# TTGO_shield_revH.net
KiCad netlist of a schematic drawn in EAGLE
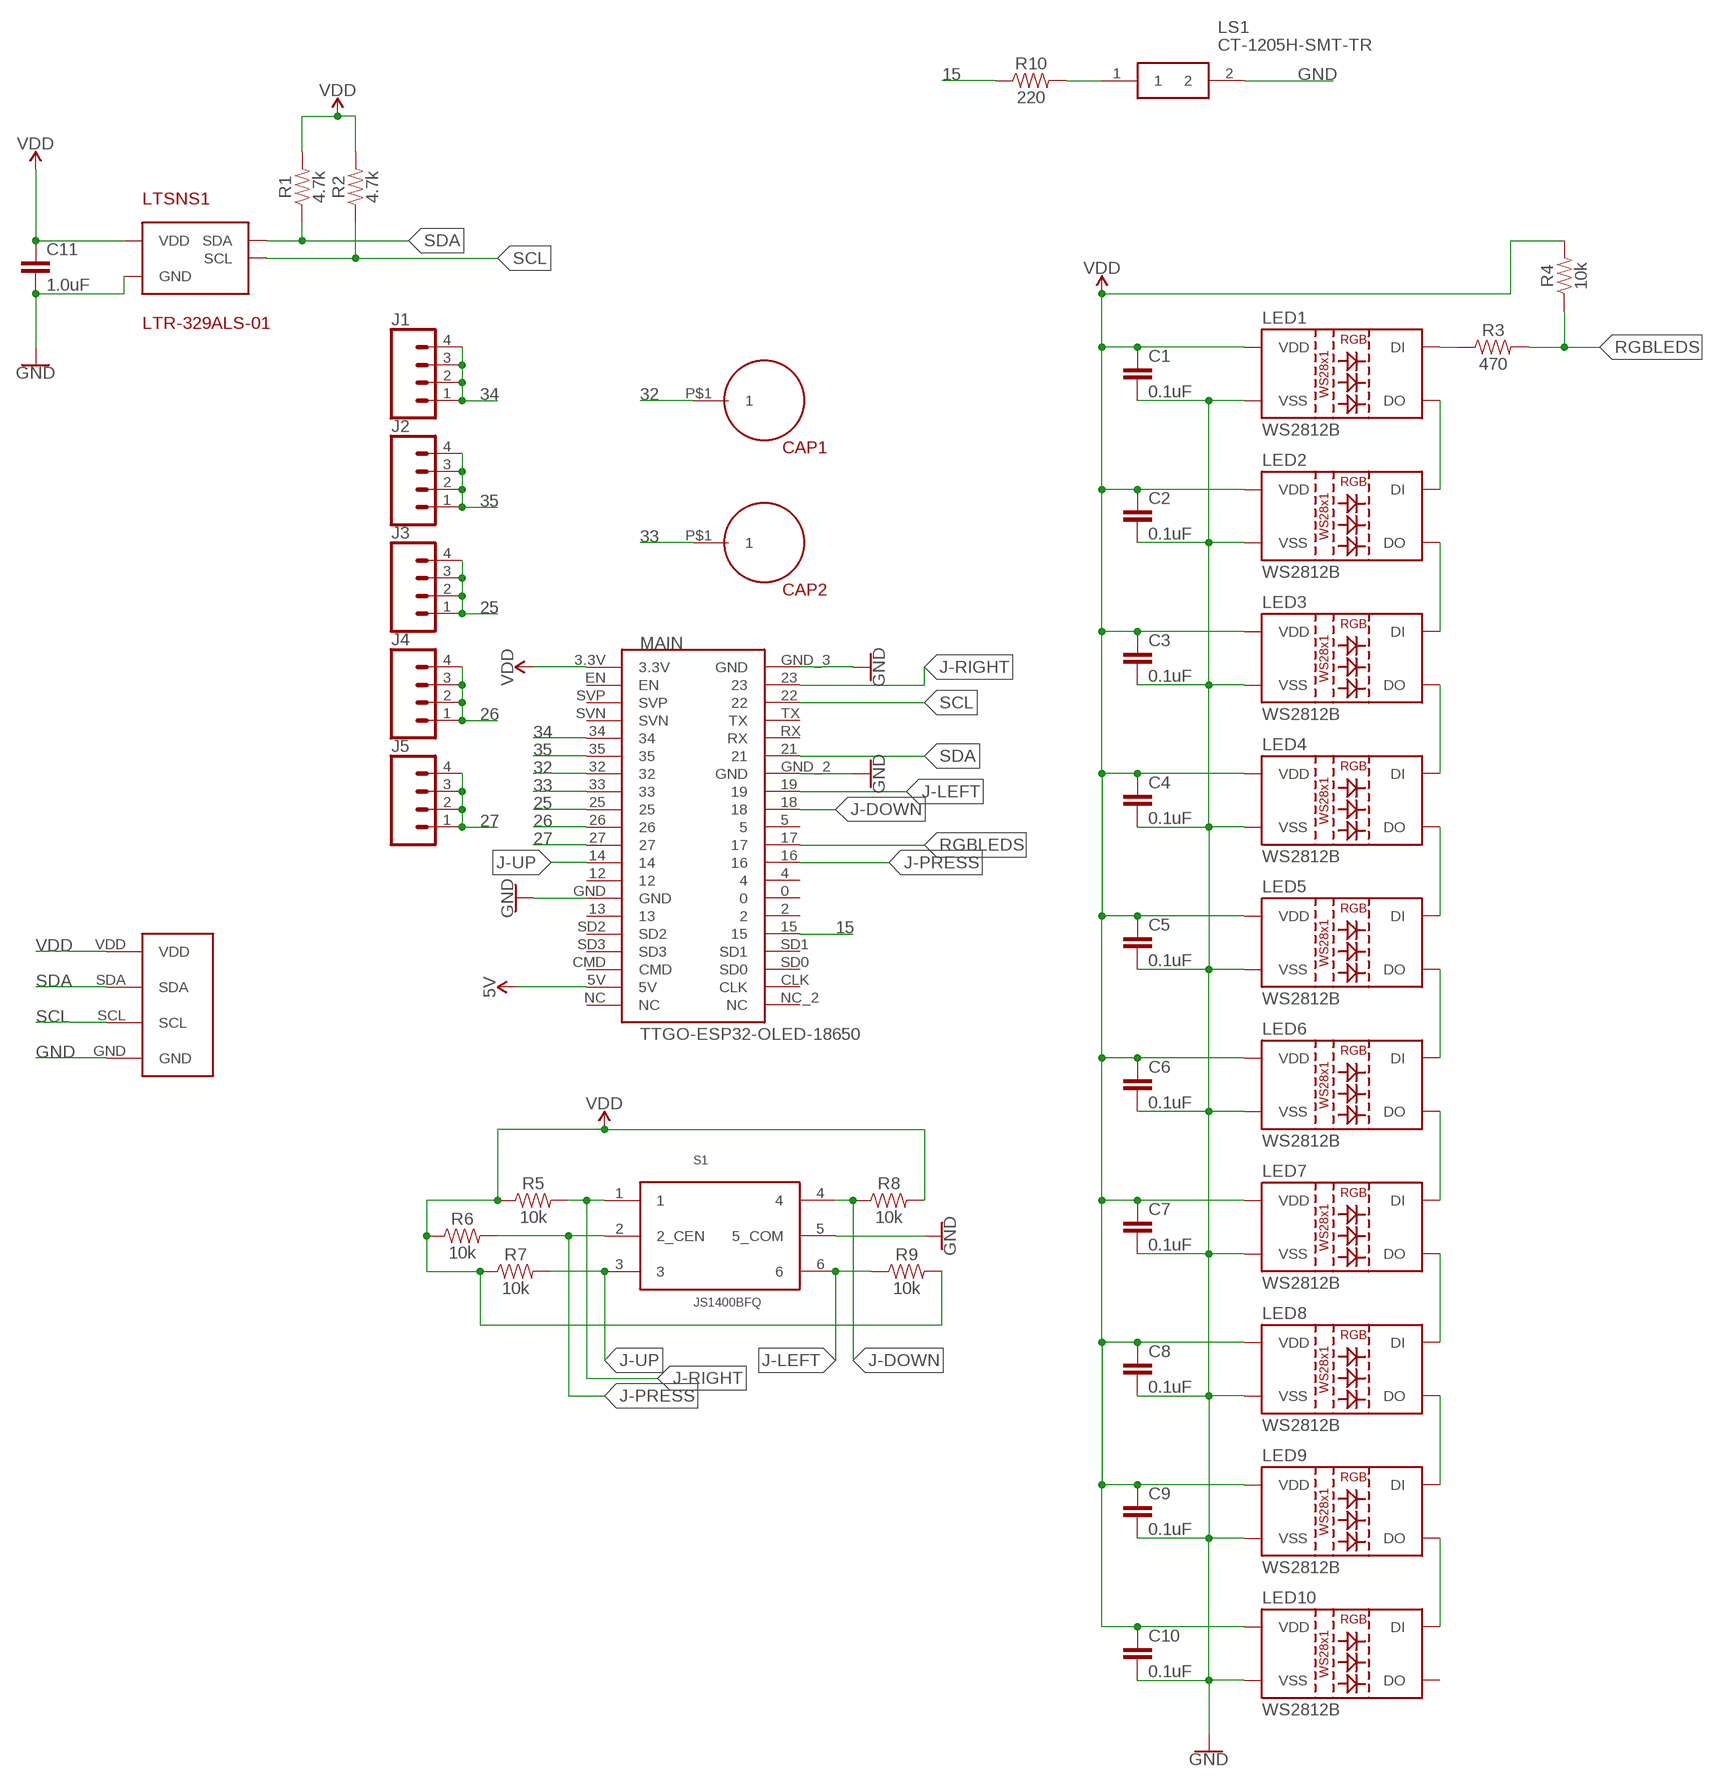
[diagram p0: schematic, sheet 1]

(export (version "E")
  (design (tool "Eeschema 10.0.6"))
  (components
    (comp (ref "C1")
      (value "0.1uF")
      (footprint "eagle-import:0603")
      (libsource (lib "eagle-import") (part "0.1UF-0603-25V-5%"))
    )
    (comp (ref "C2")
      (value "0.1uF")
      (footprint "eagle-import:0603")
      (libsource (lib "eagle-import") (part "0.1UF-0603-25V-5%"))
    )
    (comp (ref "C3")
      (value "0.1uF")
      (footprint "eagle-import:0603")
      (libsource (lib "eagle-import") (part "0.1UF-0603-25V-5%"))
    )
    (comp (ref "C4")
      (value "0.1uF")
      (footprint "eagle-import:0603")
      (libsource (lib "eagle-import") (part "0.1UF-0603-25V-5%"))
    )
    (comp (ref "C5")
      (value "0.1uF")
      (footprint "eagle-import:0603")
      (libsource (lib "eagle-import") (part "0.1UF-0603-25V-5%"))
    )
    (comp (ref "C6")
      (value "0.1uF")
      (footprint "eagle-import:0603")
      (libsource (lib "eagle-import") (part "0.1UF-0603-25V-5%"))
    )
    (comp (ref "C7")
      (value "0.1uF")
      (footprint "eagle-import:0603")
      (libsource (lib "eagle-import") (part "0.1UF-0603-25V-5%"))
    )
    (comp (ref "C8")
      (value "0.1uF")
      (footprint "eagle-import:0603")
      (libsource (lib "eagle-import") (part "0.1UF-0603-25V-5%"))
    )
    (comp (ref "C9")
      (value "0.1uF")
      (footprint "eagle-import:0603")
      (libsource (lib "eagle-import") (part "0.1UF-0603-25V-5%"))
    )
    (comp (ref "C10")
      (value "0.1uF")
      (footprint "eagle-import:0603")
      (libsource (lib "eagle-import") (part "0.1UF-0603-25V-5%"))
    )
    (comp (ref "C11")
      (value "1.0uF")
      (footprint "eagle-import:0805")
      (libsource (lib "eagle-import") (part "1.0UF-0805-25V-10%"))
    )
    (comp (ref "CAP1")
      (value "CAPSENSE_BUTTON")
      (footprint "eagle-import:CAPSENSE_BUTTON")
      (libsource (lib "eagle-import") (part "CAPSENSE_BUTTON"))
    )
    (comp (ref "CAP2")
      (value "CAPSENSE_BUTTON")
      (footprint "eagle-import:CAPSENSE_BUTTON")
      (libsource (lib "eagle-import") (part "CAPSENSE_BUTTON"))
    )
    (comp (ref "J1")
      (value "CONN_04LONGPADS")
      (footprint "eagle-import:1X04_LONGPADS")
      (libsource (lib "eagle-import") (part "CONN_04LONGPADS"))
    )
    (comp (ref "J2")
      (value "CONN_04LONGPADS")
      (footprint "eagle-import:1X04_LONGPADS")
      (libsource (lib "eagle-import") (part "CONN_04LONGPADS"))
    )
    (comp (ref "J3")
      (value "CONN_04LONGPADS")
      (footprint "eagle-import:1X04_LONGPADS")
      (libsource (lib "eagle-import") (part "CONN_04LONGPADS"))
    )
    (comp (ref "J4")
      (value "CONN_04LONGPADS")
      (footprint "eagle-import:1X04_LONGPADS")
      (libsource (lib "eagle-import") (part "CONN_04LONGPADS"))
    )
    (comp (ref "J5")
      (value "CONN_04LONGPADS")
      (footprint "eagle-import:1X04_LONGPADS")
      (libsource (lib "eagle-import") (part "CONN_04LONGPADS"))
    )
    (comp (ref "LED1")
      (value "WS2812B")
      (footprint "eagle-import:WS2812B")
      (libsource (lib "eagle-import") (part "WS2812B"))
    )
    (comp (ref "LED2")
      (value "WS2812B")
      (footprint "eagle-import:WS2812B")
      (libsource (lib "eagle-import") (part "WS2812B"))
    )
    (comp (ref "LED3")
      (value "WS2812B")
      (footprint "eagle-import:WS2812B")
      (libsource (lib "eagle-import") (part "WS2812B"))
    )
    (comp (ref "LED4")
      (value "WS2812B")
      (footprint "eagle-import:WS2812B")
      (libsource (lib "eagle-import") (part "WS2812B"))
    )
    (comp (ref "LED5")
      (value "WS2812B")
      (footprint "eagle-import:WS2812B")
      (libsource (lib "eagle-import") (part "WS2812B"))
    )
    (comp (ref "LED6")
      (value "WS2812B")
      (footprint "eagle-import:WS2812B")
      (libsource (lib "eagle-import") (part "WS2812B"))
    )
    (comp (ref "LED7")
      (value "WS2812B")
      (footprint "eagle-import:WS2812B")
      (libsource (lib "eagle-import") (part "WS2812B"))
    )
    (comp (ref "LED8")
      (value "WS2812B")
      (footprint "eagle-import:WS2812B")
      (libsource (lib "eagle-import") (part "WS2812B"))
    )
    (comp (ref "LED9")
      (value "WS2812B")
      (footprint "eagle-import:WS2812B")
      (libsource (lib "eagle-import") (part "WS2812B"))
    )
    (comp (ref "LED10")
      (value "WS2812B")
      (footprint "eagle-import:WS2812B")
      (libsource (lib "eagle-import") (part "WS2812B"))
    )
    (comp (ref "LS1")
      (value "CT-1205H-SMT-TR")
      (footprint "eagle-import:CT1205HSMTTR")
      (libsource (lib "eagle-import") (part "CT-1205H-SMT-TR"))
    )
    (comp (ref "LTSNS1")
      (value "LTR-329ALS-01")
      (footprint "eagle-import:CHIPLED-4")
      (libsource (lib "eagle-import") (part "LTR-329ALS-01"))
    )
    (comp (ref "MAIN")
      (value "TTGO-ESP32-OLED-18650")
      (footprint "eagle-import:TTGO-ESP32-OLED-18650")
      (libsource (lib "eagle-import") (part "TTGO-ESP32-OLED-18650"))
    )
    (comp (ref "R1")
      (value "4.7k")
      (footprint "eagle-import:0603")
      (libsource (lib "eagle-import") (part "4.7KOHM-0603-1/10W-1%"))
    )
    (comp (ref "R2")
      (value "4.7k")
      (footprint "eagle-import:0603")
      (libsource (lib "eagle-import") (part "4.7KOHM-0603-1/10W-1%"))
    )
    (comp (ref "R3")
      (value "470")
      (footprint "eagle-import:0603")
      (libsource (lib "eagle-import") (part "470OHM-0603-1/10W-1%"))
    )
    (comp (ref "R4")
      (value "10k")
      (footprint "eagle-import:0603")
      (libsource (lib "eagle-import") (part "10KOHM-0603-1/10W-1%"))
    )
    (comp (ref "R5")
      (value "10k")
      (footprint "eagle-import:0603")
      (libsource (lib "eagle-import") (part "10KOHM-0603-1/10W-1%"))
    )
    (comp (ref "R6")
      (value "10k")
      (footprint "eagle-import:0603")
      (libsource (lib "eagle-import") (part "10KOHM-0603-1/10W-1%"))
    )
    (comp (ref "R7")
      (value "10k")
      (footprint "eagle-import:0603")
      (libsource (lib "eagle-import") (part "10KOHM-0603-1/10W-1%"))
    )
    (comp (ref "R8")
      (value "10k")
      (footprint "eagle-import:0603")
      (libsource (lib "eagle-import") (part "10KOHM-0603-1/10W-1%"))
    )
    (comp (ref "R9")
      (value "10k")
      (footprint "eagle-import:0603")
      (libsource (lib "eagle-import") (part "10KOHM-0603-1/10W-1%"))
    )
    (comp (ref "R10")
      (value "220")
      (footprint "eagle-import:0603")
      (libsource (lib "eagle-import") (part "470OHM-0603-1/10W-1%"))
    )
    (comp (ref "S1")
      (value "JS1400BFQ")
      (footprint "eagle-import:JS1400BFQ")
      (libsource (lib "eagle-import") (part "JS1400BFQ"))
    )
    (comp (ref "U$2")
      (value "I2C-FEMALE-HEADER")
      (footprint "eagle-import:I2C-FEMALE-HEADER")
      (libsource (lib "eagle-import") (part "I2C-FEMALE-HEADER"))
    )
  )
  (nets
    (net (code "1") (name "/15") (class "Default")
      (node (ref "MAIN") (pin "15") (pinfunction "15_15") (pintype "bidirectional"))
      (node (ref "R10") (pin "1") (pinfunction "1_1") (pintype "passive"))
    )
    (net (code "2") (name "/25") (class "Default")
      (node (ref "J3") (pin "1") (pinfunction "1_1") (pintype "passive"))
      (node (ref "J3") (pin "2") (pinfunction "2_2") (pintype "passive"))
      (node (ref "J3") (pin "3") (pinfunction "3_3") (pintype "passive"))
      (node (ref "J3") (pin "4") (pinfunction "4_4") (pintype "passive"))
      (node (ref "MAIN") (pin "25") (pinfunction "25_25") (pintype "bidirectional"))
    )
    (net (code "3") (name "/26") (class "Default")
      (node (ref "J4") (pin "1") (pinfunction "1_1") (pintype "passive"))
      (node (ref "J4") (pin "2") (pinfunction "2_2") (pintype "passive"))
      (node (ref "J4") (pin "3") (pinfunction "3_3") (pintype "passive"))
      (node (ref "J4") (pin "4") (pinfunction "4_4") (pintype "passive"))
      (node (ref "MAIN") (pin "26") (pinfunction "26_26") (pintype "bidirectional"))
    )
    (net (code "4") (name "/27") (class "Default")
      (node (ref "J5") (pin "1") (pinfunction "1_1") (pintype "passive"))
      (node (ref "J5") (pin "2") (pinfunction "2_2") (pintype "passive"))
      (node (ref "J5") (pin "3") (pinfunction "3_3") (pintype "passive"))
      (node (ref "J5") (pin "4") (pinfunction "4_4") (pintype "passive"))
      (node (ref "MAIN") (pin "27") (pinfunction "27_27") (pintype "bidirectional"))
    )
    (net (code "5") (name "/32") (class "Default")
      (node (ref "CAP1") (pin "P$1") (pinfunction "1_P$1") (pintype "bidirectional"))
      (node (ref "MAIN") (pin "32") (pinfunction "32_32") (pintype "bidirectional"))
    )
    (net (code "6") (name "/33") (class "Default")
      (node (ref "CAP2") (pin "P$1") (pinfunction "1_P$1") (pintype "bidirectional"))
      (node (ref "MAIN") (pin "33") (pinfunction "33_33") (pintype "bidirectional"))
    )
    (net (code "7") (name "/34") (class "Default")
      (node (ref "J1") (pin "1") (pinfunction "1_1") (pintype "passive"))
      (node (ref "J1") (pin "2") (pinfunction "2_2") (pintype "passive"))
      (node (ref "J1") (pin "3") (pinfunction "3_3") (pintype "passive"))
      (node (ref "J1") (pin "4") (pinfunction "4_4") (pintype "passive"))
      (node (ref "MAIN") (pin "34") (pinfunction "34_34") (pintype "bidirectional"))
    )
    (net (code "8") (name "/35") (class "Default")
      (node (ref "J2") (pin "1") (pinfunction "1_1") (pintype "passive"))
      (node (ref "J2") (pin "2") (pinfunction "2_2") (pintype "passive"))
      (node (ref "J2") (pin "3") (pinfunction "3_3") (pintype "passive"))
      (node (ref "J2") (pin "4") (pinfunction "4_4") (pintype "passive"))
      (node (ref "MAIN") (pin "35") (pinfunction "35_35") (pintype "bidirectional"))
    )
    (net (code "9") (name "5V") (class "Default")
      (node (ref "MAIN") (pin "5V") (pinfunction "5V_5V") (pintype "bidirectional"))
    )
    (net (code "10") (name "GND") (class "Default")
      (node (ref "C1") (pin "2") (pinfunction "2_2") (pintype "passive"))
      (node (ref "C10") (pin "2") (pinfunction "2_2") (pintype "passive"))
      (node (ref "C11") (pin "2") (pinfunction "2_2") (pintype "passive"))
      (node (ref "C2") (pin "2") (pinfunction "2_2") (pintype "passive"))
      (node (ref "C3") (pin "2") (pinfunction "2_2") (pintype "passive"))
      (node (ref "C4") (pin "2") (pinfunction "2_2") (pintype "passive"))
      (node (ref "C5") (pin "2") (pinfunction "2_2") (pintype "passive"))
      (node (ref "C6") (pin "2") (pinfunction "2_2") (pintype "passive"))
      (node (ref "C7") (pin "2") (pinfunction "2_2") (pintype "passive"))
      (node (ref "C8") (pin "2") (pinfunction "2_2") (pintype "passive"))
      (node (ref "C9") (pin "2") (pinfunction "2_2") (pintype "passive"))
      (node (ref "LED1") (pin "3") (pinfunction "VSS_3") (pintype "bidirectional"))
      (node (ref "LED10") (pin "3") (pinfunction "VSS_3") (pintype "bidirectional"))
      (node (ref "LED2") (pin "3") (pinfunction "VSS_3") (pintype "bidirectional"))
      (node (ref "LED3") (pin "3") (pinfunction "VSS_3") (pintype "bidirectional"))
      (node (ref "LED4") (pin "3") (pinfunction "VSS_3") (pintype "bidirectional"))
      (node (ref "LED5") (pin "3") (pinfunction "VSS_3") (pintype "bidirectional"))
      (node (ref "LED6") (pin "3") (pinfunction "VSS_3") (pintype "bidirectional"))
      (node (ref "LED7") (pin "3") (pinfunction "VSS_3") (pintype "bidirectional"))
      (node (ref "LED8") (pin "3") (pinfunction "VSS_3") (pintype "bidirectional"))
      (node (ref "LED9") (pin "3") (pinfunction "VSS_3") (pintype "bidirectional"))
      (node (ref "LS1") (pin "2") (pinfunction "2_2") (pintype "bidirectional"))
      (node (ref "LTSNS1") (pin "2") (pinfunction "GND_2") (pintype "bidirectional"))
      (node (ref "MAIN") (pin "GND") (pinfunction "GND_GND") (pintype "bidirectional"))
      (node (ref "MAIN") (pin "GND_2") (pinfunction "GND_GND_2") (pintype "bidirectional"))
      (node (ref "MAIN") (pin "GND_3") (pinfunction "GND_GND_3") (pintype "bidirectional"))
      (node (ref "S1") (pin "5") (pinfunction "5_COM_5") (pintype "bidirectional"))
      (node (ref "U$2") (pin "GND") (pinfunction "GND_GND") (pintype "bidirectional"))
    )
    (net (code "11") (name "J-DOWN") (class "Default")
      (node (ref "MAIN") (pin "18") (pinfunction "18_18") (pintype "bidirectional"))
      (node (ref "R8") (pin "1") (pinfunction "1_1") (pintype "passive"))
      (node (ref "S1") (pin "4") (pinfunction "4_4") (pintype "bidirectional"))
    )
    (net (code "12") (name "J-LEFT") (class "Default")
      (node (ref "MAIN") (pin "19") (pinfunction "19_19") (pintype "bidirectional"))
      (node (ref "R9") (pin "1") (pinfunction "1_1") (pintype "passive"))
      (node (ref "S1") (pin "6") (pinfunction "6_6") (pintype "bidirectional"))
    )
    (net (code "13") (name "J-PRESS") (class "Default")
      (node (ref "MAIN") (pin "16") (pinfunction "16_16") (pintype "bidirectional"))
      (node (ref "R6") (pin "2") (pinfunction "2_2") (pintype "passive"))
      (node (ref "S1") (pin "2") (pinfunction "2_CEN_2") (pintype "bidirectional"))
    )
    (net (code "14") (name "J-RIGHT") (class "Default")
      (node (ref "MAIN") (pin "23") (pinfunction "23_23") (pintype "bidirectional"))
      (node (ref "R5") (pin "2") (pinfunction "2_2") (pintype "passive"))
      (node (ref "S1") (pin "1") (pinfunction "1_1") (pintype "bidirectional"))
    )
    (net (code "15") (name "J-UP") (class "Default")
      (node (ref "MAIN") (pin "14") (pinfunction "14_14") (pintype "bidirectional"))
      (node (ref "R7") (pin "2") (pinfunction "2_2") (pintype "passive"))
      (node (ref "S1") (pin "3") (pinfunction "3_3") (pintype "bidirectional"))
    )
    (net (code "16") (name "Net-(LED1-DI)") (class "Default")
      (node (ref "LED1") (pin "4") (pinfunction "DI_4") (pintype "bidirectional"))
      (node (ref "R3") (pin "1") (pinfunction "1_1") (pintype "passive"))
    )
    (net (code "17") (name "Net-(LED1-DO)") (class "Default")
      (node (ref "LED1") (pin "2") (pinfunction "DO_2") (pintype "bidirectional"))
      (node (ref "LED2") (pin "4") (pinfunction "DI_4") (pintype "bidirectional"))
    )
    (net (code "18") (name "Net-(LED2-DO)") (class "Default")
      (node (ref "LED2") (pin "2") (pinfunction "DO_2") (pintype "bidirectional"))
      (node (ref "LED3") (pin "4") (pinfunction "DI_4") (pintype "bidirectional"))
    )
    (net (code "19") (name "Net-(LED3-DO)") (class "Default")
      (node (ref "LED3") (pin "2") (pinfunction "DO_2") (pintype "bidirectional"))
      (node (ref "LED4") (pin "4") (pinfunction "DI_4") (pintype "bidirectional"))
    )
    (net (code "20") (name "Net-(LED4-DO)") (class "Default")
      (node (ref "LED4") (pin "2") (pinfunction "DO_2") (pintype "bidirectional"))
      (node (ref "LED5") (pin "4") (pinfunction "DI_4") (pintype "bidirectional"))
    )
    (net (code "21") (name "Net-(LED5-DO)") (class "Default")
      (node (ref "LED5") (pin "2") (pinfunction "DO_2") (pintype "bidirectional"))
      (node (ref "LED6") (pin "4") (pinfunction "DI_4") (pintype "bidirectional"))
    )
    (net (code "22") (name "Net-(LED6-DO)") (class "Default")
      (node (ref "LED6") (pin "2") (pinfunction "DO_2") (pintype "bidirectional"))
      (node (ref "LED7") (pin "4") (pinfunction "DI_4") (pintype "bidirectional"))
    )
    (net (code "23") (name "Net-(LED7-DO)") (class "Default")
      (node (ref "LED7") (pin "2") (pinfunction "DO_2") (pintype "bidirectional"))
      (node (ref "LED8") (pin "4") (pinfunction "DI_4") (pintype "bidirectional"))
    )
    (net (code "24") (name "Net-(LED8-DO)") (class "Default")
      (node (ref "LED8") (pin "2") (pinfunction "DO_2") (pintype "bidirectional"))
      (node (ref "LED9") (pin "4") (pinfunction "DI_4") (pintype "bidirectional"))
    )
    (net (code "25") (name "Net-(LED10-DI)") (class "Default")
      (node (ref "LED10") (pin "4") (pinfunction "DI_4") (pintype "bidirectional"))
      (node (ref "LED9") (pin "2") (pinfunction "DO_2") (pintype "bidirectional"))
    )
    (net (code "26") (name "Net-(LS1-Pad1)") (class "Default")
      (node (ref "LS1") (pin "1") (pinfunction "1_1") (pintype "bidirectional"))
      (node (ref "R10") (pin "2") (pinfunction "2_2") (pintype "passive"))
    )
    (net (code "27") (name "RGBLEDS") (class "Default")
      (node (ref "MAIN") (pin "17") (pinfunction "17_17") (pintype "bidirectional"))
      (node (ref "R3") (pin "2") (pinfunction "2_2") (pintype "passive"))
      (node (ref "R4") (pin "1") (pinfunction "1_1") (pintype "passive"))
    )
    (net (code "28") (name "SCL") (class "Default")
      (node (ref "LTSNS1") (pin "4") (pinfunction "SCL_4") (pintype "bidirectional"))
      (node (ref "MAIN") (pin "22") (pinfunction "22_22") (pintype "bidirectional"))
      (node (ref "R2") (pin "1") (pinfunction "1_1") (pintype "passive"))
      (node (ref "U$2") (pin "SCL") (pinfunction "SCL_SCL") (pintype "bidirectional"))
    )
    (net (code "29") (name "SDA") (class "Default")
      (node (ref "LTSNS1") (pin "3") (pinfunction "SDA_3") (pintype "bidirectional"))
      (node (ref "MAIN") (pin "21") (pinfunction "21_21") (pintype "bidirectional"))
      (node (ref "R1") (pin "1") (pinfunction "1_1") (pintype "passive"))
      (node (ref "U$2") (pin "SDA") (pinfunction "SDA_SDA") (pintype "bidirectional"))
    )
    (net (code "30") (name "VDD") (class "Default")
      (node (ref "C1") (pin "1") (pinfunction "1_1") (pintype "passive"))
      (node (ref "C10") (pin "1") (pinfunction "1_1") (pintype "passive"))
      (node (ref "C11") (pin "1") (pinfunction "1_1") (pintype "passive"))
      (node (ref "C2") (pin "1") (pinfunction "1_1") (pintype "passive"))
      (node (ref "C3") (pin "1") (pinfunction "1_1") (pintype "passive"))
      (node (ref "C4") (pin "1") (pinfunction "1_1") (pintype "passive"))
      (node (ref "C5") (pin "1") (pinfunction "1_1") (pintype "passive"))
      (node (ref "C6") (pin "1") (pinfunction "1_1") (pintype "passive"))
      (node (ref "C7") (pin "1") (pinfunction "1_1") (pintype "passive"))
      (node (ref "C8") (pin "1") (pinfunction "1_1") (pintype "passive"))
      (node (ref "C9") (pin "1") (pinfunction "1_1") (pintype "passive"))
      (node (ref "LED1") (pin "1") (pinfunction "VDD_1") (pintype "bidirectional"))
      (node (ref "LED10") (pin "1") (pinfunction "VDD_1") (pintype "bidirectional"))
      (node (ref "LED2") (pin "1") (pinfunction "VDD_1") (pintype "bidirectional"))
      (node (ref "LED3") (pin "1") (pinfunction "VDD_1") (pintype "bidirectional"))
      (node (ref "LED4") (pin "1") (pinfunction "VDD_1") (pintype "bidirectional"))
      (node (ref "LED5") (pin "1") (pinfunction "VDD_1") (pintype "bidirectional"))
      (node (ref "LED6") (pin "1") (pinfunction "VDD_1") (pintype "bidirectional"))
      (node (ref "LED7") (pin "1") (pinfunction "VDD_1") (pintype "bidirectional"))
      (node (ref "LED8") (pin "1") (pinfunction "VDD_1") (pintype "bidirectional"))
      (node (ref "LED9") (pin "1") (pinfunction "VDD_1") (pintype "bidirectional"))
      (node (ref "LTSNS1") (pin "1") (pinfunction "VDD_1") (pintype "bidirectional"))
      (node (ref "MAIN") (pin "3.3V") (pinfunction "3.3V_3.3V") (pintype "bidirectional"))
      (node (ref "R1") (pin "2") (pinfunction "2_2") (pintype "passive"))
      (node (ref "R2") (pin "2") (pinfunction "2_2") (pintype "passive"))
      (node (ref "R4") (pin "2") (pinfunction "2_2") (pintype "passive"))
      (node (ref "R5") (pin "1") (pinfunction "1_1") (pintype "passive"))
      (node (ref "R6") (pin "1") (pinfunction "1_1") (pintype "passive"))
      (node (ref "R7") (pin "1") (pinfunction "1_1") (pintype "passive"))
      (node (ref "R8") (pin "2") (pinfunction "2_2") (pintype "passive"))
      (node (ref "R9") (pin "2") (pinfunction "2_2") (pintype "passive"))
      (node (ref "U$2") (pin "VDD") (pinfunction "VDD_VDD") (pintype "bidirectional"))
    )
    (net (code "31") (name "unconnected-(LED10-DO-Pad2)") (class "Default")
      (node (ref "LED10") (pin "2") (pinfunction "DO_2") (pintype "bidirectional"))
    )
    (net (code "32") (name "unconnected-(MAIN-NC-PadNC_2)") (class "Default")
      (node (ref "MAIN") (pin "NC_2") (pinfunction "NC_NC_2") (pintype "bidirectional"))
    )
    (net (code "33") (name "unconnected-(MAIN-Pad0)") (class "Default")
      (node (ref "MAIN") (pin "0") (pinfunction "0_0") (pintype "bidirectional"))
    )
    (net (code "34") (name "unconnected-(MAIN-Pad2)") (class "Default")
      (node (ref "MAIN") (pin "2") (pinfunction "2_2") (pintype "bidirectional"))
    )
    (net (code "35") (name "unconnected-(MAIN-Pad4)") (class "Default")
      (node (ref "MAIN") (pin "4") (pinfunction "4_4") (pintype "bidirectional"))
    )
    (net (code "36") (name "unconnected-(MAIN-Pad5)") (class "Default")
      (node (ref "MAIN") (pin "5") (pinfunction "5_5") (pintype "bidirectional"))
    )
    (net (code "37") (name "unconnected-(MAIN-Pad12)") (class "Default")
      (node (ref "MAIN") (pin "12") (pinfunction "12_12") (pintype "bidirectional"))
    )
    (net (code "38") (name "unconnected-(MAIN-Pad13)") (class "Default")
      (node (ref "MAIN") (pin "13") (pinfunction "13_13") (pintype "bidirectional"))
    )
    (net (code "39") (name "unconnected-(MAIN-PadCLK)") (class "Default")
      (node (ref "MAIN") (pin "CLK") (pinfunction "CLK_CLK") (pintype "bidirectional"))
    )
    (net (code "40") (name "unconnected-(MAIN-PadCMD)") (class "Default")
      (node (ref "MAIN") (pin "CMD") (pinfunction "CMD_CMD") (pintype "bidirectional"))
    )
    (net (code "41") (name "unconnected-(MAIN-PadEN)") (class "Default")
      (node (ref "MAIN") (pin "EN") (pinfunction "EN_EN") (pintype "bidirectional"))
    )
    (net (code "42") (name "unconnected-(MAIN-PadNC)") (class "Default")
      (node (ref "MAIN") (pin "NC") (pinfunction "NC_NC") (pintype "bidirectional"))
    )
    (net (code "43") (name "unconnected-(MAIN-PadRX)") (class "Default")
      (node (ref "MAIN") (pin "RX") (pinfunction "RX_RX") (pintype "bidirectional"))
    )
    (net (code "44") (name "unconnected-(MAIN-PadSD0)") (class "Default")
      (node (ref "MAIN") (pin "SD0") (pinfunction "SD0_SD0") (pintype "bidirectional"))
    )
    (net (code "45") (name "unconnected-(MAIN-PadSD1)") (class "Default")
      (node (ref "MAIN") (pin "SD1") (pinfunction "SD1_SD1") (pintype "bidirectional"))
    )
    (net (code "46") (name "unconnected-(MAIN-PadSD2)") (class "Default")
      (node (ref "MAIN") (pin "SD2") (pinfunction "SD2_SD2") (pintype "bidirectional"))
    )
    (net (code "47") (name "unconnected-(MAIN-PadSD3)") (class "Default")
      (node (ref "MAIN") (pin "SD3") (pinfunction "SD3_SD3") (pintype "bidirectional"))
    )
    (net (code "48") (name "unconnected-(MAIN-PadSVN)") (class "Default")
      (node (ref "MAIN") (pin "SVN") (pinfunction "SVN_SVN") (pintype "bidirectional"))
    )
    (net (code "49") (name "unconnected-(MAIN-PadSVP)") (class "Default")
      (node (ref "MAIN") (pin "SVP") (pinfunction "SVP_SVP") (pintype "bidirectional"))
    )
    (net (code "50") (name "unconnected-(MAIN-PadTX)") (class "Default")
      (node (ref "MAIN") (pin "TX") (pinfunction "TX_TX") (pintype "bidirectional"))
    )
  )
)
